# ESP_LoRa_1_1.net
KiCad netlist of a schematic drawn in EAGLE
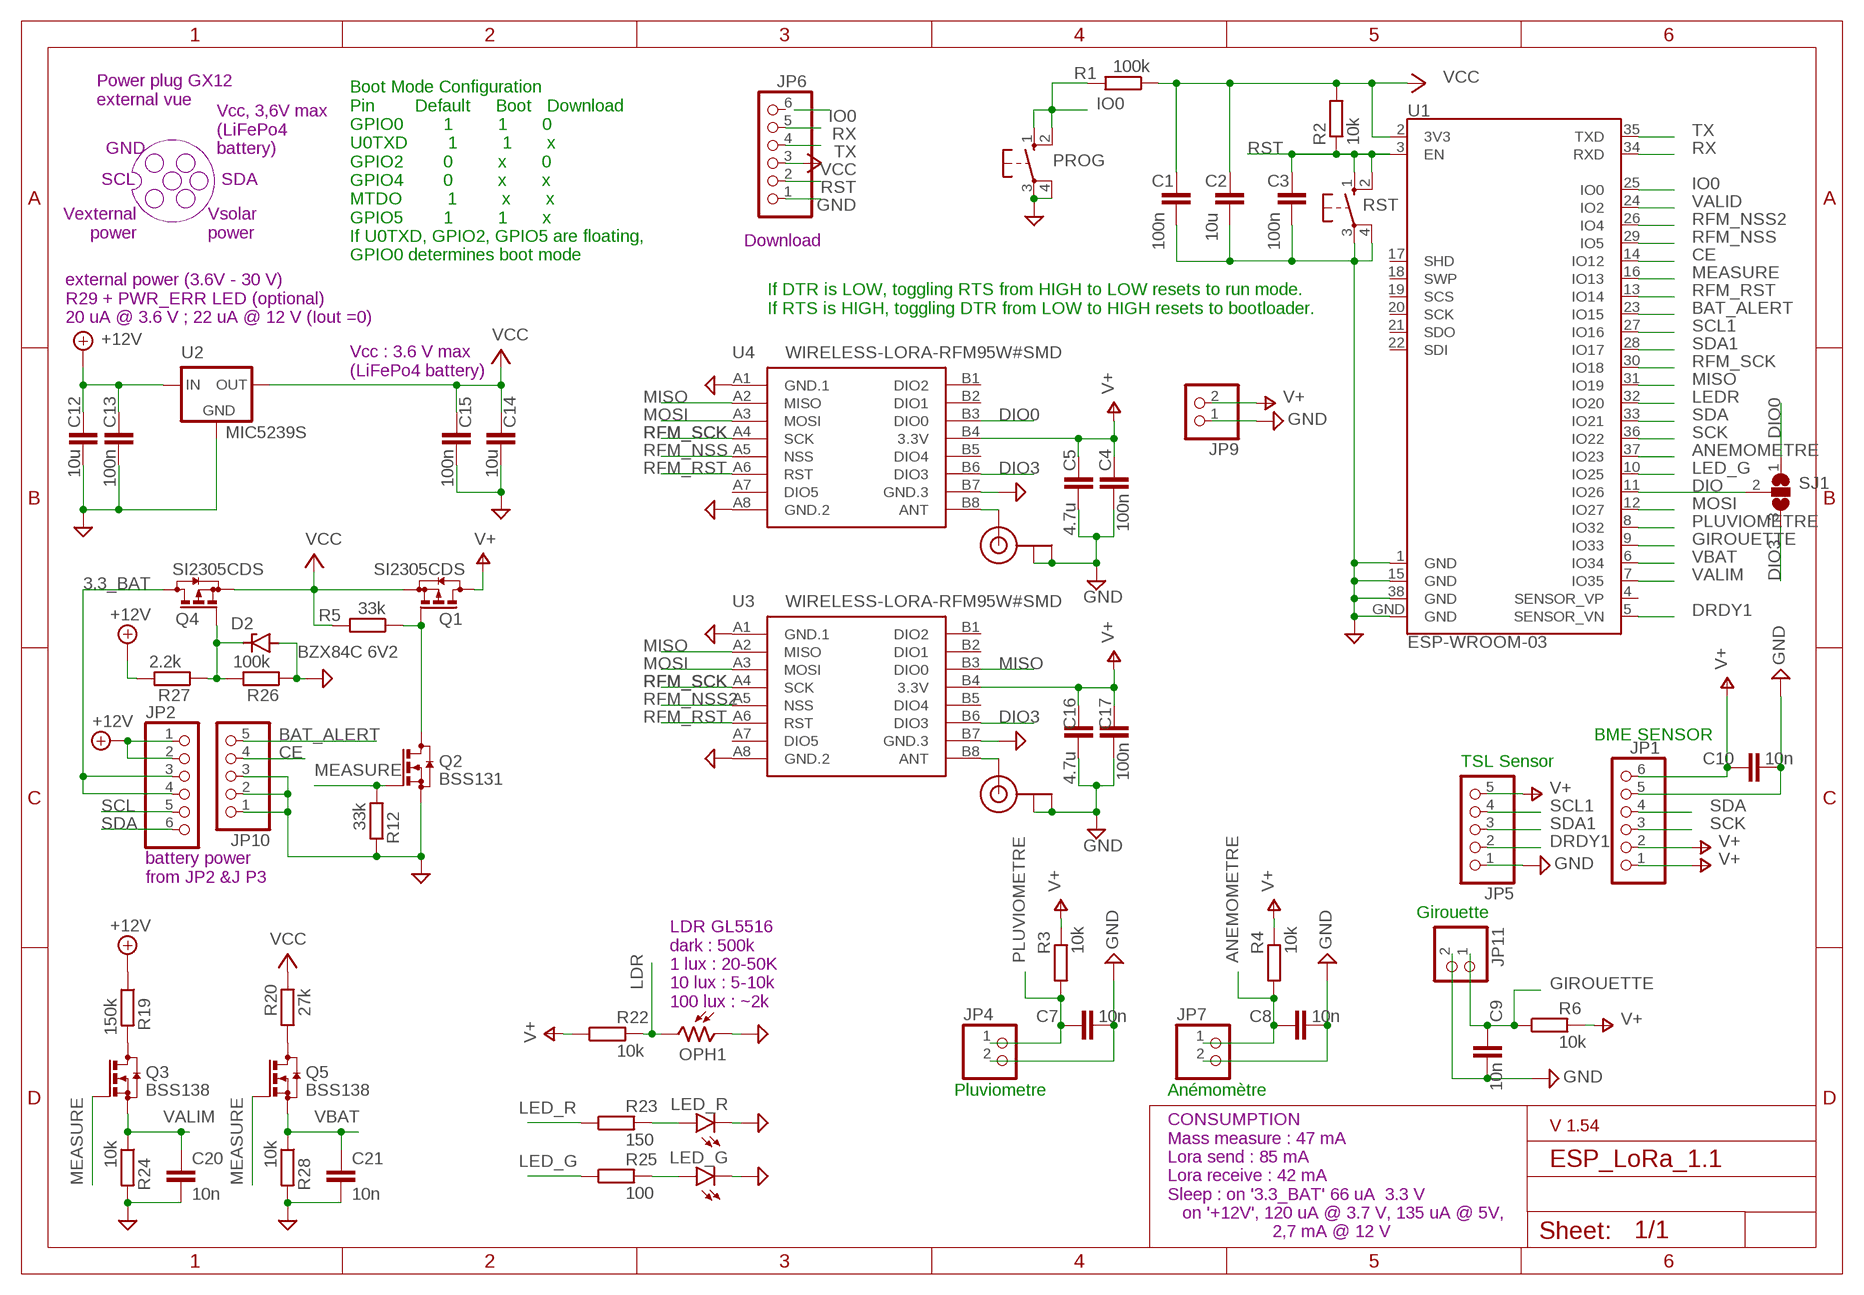
[diagram p0: schematic, sheet 1]

(export (version "E")
  (design (tool "Eeschema 10.0.6"))
  (components
    (comp (ref "C1")
      (value "100n")
      (footprint "eagle-import:C1206")
      (libsource (lib "eagle-import") (part "CC1206"))
    )
    (comp (ref "C2")
      (value "10u")
      (footprint "eagle-import:C1210")
      (libsource (lib "eagle-import") (part "CC1210"))
    )
    (comp (ref "C3")
      (value "100n")
      (footprint "eagle-import:C1206")
      (libsource (lib "eagle-import") (part "CC1206"))
    )
    (comp (ref "C4")
      (value "100n")
      (footprint "eagle-import:C1206")
      (libsource (lib "eagle-import") (part "CC1206"))
    )
    (comp (ref "C5")
      (value "4.7u")
      (footprint "eagle-import:C1210")
      (libsource (lib "eagle-import") (part "CC1210"))
    )
    (comp (ref "C7")
      (value "10n")
      (footprint "eagle-import:C1206")
      (libsource (lib "eagle-import") (part "CC1206"))
    )
    (comp (ref "C8")
      (value "10n")
      (footprint "eagle-import:C1206")
      (libsource (lib "eagle-import") (part "CC1206"))
    )
    (comp (ref "C9")
      (value "10n")
      (footprint "eagle-import:C1206")
      (libsource (lib "eagle-import") (part "CC1206"))
    )
    (comp (ref "C10")
      (value "10n")
      (footprint "eagle-import:C1206")
      (libsource (lib "eagle-import") (part "CC1206"))
    )
    (comp (ref "C12")
      (value "10u")
      (footprint "eagle-import:C1210")
      (libsource (lib "eagle-import") (part "CC1210"))
    )
    (comp (ref "C13")
      (value "100n")
      (footprint "eagle-import:C1206")
      (libsource (lib "eagle-import") (part "CC1206"))
    )
    (comp (ref "C14")
      (value "10u")
      (footprint "eagle-import:C1210")
      (libsource (lib "eagle-import") (part "CC1210"))
    )
    (comp (ref "C15")
      (value "100n")
      (footprint "eagle-import:C1206")
      (libsource (lib "eagle-import") (part "CC1206"))
    )
    (comp (ref "C16")
      (value "4.7u")
      (footprint "eagle-import:C1210")
      (libsource (lib "eagle-import") (part "CC1210"))
    )
    (comp (ref "C17")
      (value "100n")
      (footprint "eagle-import:C1206")
      (libsource (lib "eagle-import") (part "CC1206"))
    )
    (comp (ref "C20")
      (value "10n")
      (footprint "eagle-import:C1206")
      (libsource (lib "eagle-import") (part "CC1206"))
    )
    (comp (ref "C21")
      (value "10n")
      (footprint "eagle-import:C1206")
      (libsource (lib "eagle-import") (part "CC1206"))
    )
    (comp (ref "D2")
      (value "BZX84C 6V2")
      (footprint "eagle-import:TO236")
      (libsource (lib "eagle-import") (part "BZX84CSMD"))
    )
    (comp (ref "J1")
      (value "U.FL")
      (footprint "eagle-import:U.FL")
      (libsource (lib "eagle-import") (part "U.FL"))
    )
    (comp (ref "J2")
      (value "U.FL")
      (footprint "eagle-import:U.FL")
      (libsource (lib "eagle-import") (part "U.FL"))
    )
    (comp (ref "JP1")
      (value "PINHD-1X6")
      (footprint "eagle-import:1X06")
      (libsource (lib "eagle-import") (part "PINHD-1X6"))
    )
    (comp (ref "JP2")
      (value "PINHD-1X6")
      (footprint "eagle-import:1X06")
      (libsource (lib "eagle-import") (part "PINHD-1X6"))
    )
    (comp (ref "JP4")
      (value "PINHD-1X2")
      (footprint "eagle-import:1X02")
      (libsource (lib "eagle-import") (part "PINHD-1X2"))
    )
    (comp (ref "JP5")
      (value "PINHD-1X5")
      (footprint "eagle-import:1X05")
      (libsource (lib "eagle-import") (part "PINHD-1X5"))
    )
    (comp (ref "JP6")
      (value "PINHD-1X6")
      (footprint "eagle-import:1X06")
      (libsource (lib "eagle-import") (part "PINHD-1X6"))
    )
    (comp (ref "JP7")
      (value "PINHD-1X2")
      (footprint "eagle-import:1X02")
      (libsource (lib "eagle-import") (part "PINHD-1X2"))
    )
    (comp (ref "JP9")
      (value "PINHD-1X2")
      (footprint "eagle-import:1X02")
      (libsource (lib "eagle-import") (part "PINHD-1X2"))
    )
    (comp (ref "JP10")
      (value "PINHD-1X5")
      (footprint "eagle-import:1X05")
      (libsource (lib "eagle-import") (part "PINHD-1X5"))
    )
    (comp (ref "JP11")
      (value "PINHD-1X2")
      (footprint "eagle-import:1X02")
      (libsource (lib "eagle-import") (part "PINHD-1X2"))
    )
    (comp (ref "LED_G")
      (value "LEDSMT1206")
      (footprint "eagle-import:1206")
      (libsource (lib "eagle-import") (part "LEDSMT1206"))
    )
    (comp (ref "LED_R")
      (value "LEDSMT1206")
      (footprint "eagle-import:1206")
      (libsource (lib "eagle-import") (part "LEDSMT1206"))
    )
    (comp (ref "OPH1")
      (value "VT93N2")
      (footprint "eagle-import:VT900")
      (libsource (lib "eagle-import") (part "VT93N2"))
    )
    (comp (ref "PROG")
      (value "10-XX")
      (footprint "eagle-import:B3F-10XX")
      (fields (field (name "MPN") "B3F-1000"))
      (libsource (lib "eagle-import") (part "10-XX"))
    )
    (comp (ref "Q1")
      (value "SI2305CDS")
      (footprint "eagle-import:SOT23")
      (libsource (lib "eagle-import") (part "SI2305CDS"))
    )
    (comp (ref "Q2")
      (value "BSS131")
      (footprint "eagle-import:SOT23")
      (libsource (lib "eagle-import") (part "BSS131"))
    )
    (comp (ref "Q3")
      (value "BSS138")
      (footprint "eagle-import:SOT23")
      (libsource (lib "eagle-import") (part "BSS138"))
    )
    (comp (ref "Q4")
      (value "SI2305CDS")
      (footprint "eagle-import:SOT23")
      (libsource (lib "eagle-import") (part "SI2305CDS"))
    )
    (comp (ref "Q5")
      (value "BSS138")
      (footprint "eagle-import:SOT23")
      (libsource (lib "eagle-import") (part "BSS138"))
    )
    (comp (ref "R1")
      (value "100k")
      (footprint "eagle-import:R1206")
      (libsource (lib "eagle-import") (part "RR1206"))
    )
    (comp (ref "R2")
      (value "10k")
      (footprint "eagle-import:R1206")
      (libsource (lib "eagle-import") (part "RR1206"))
    )
    (comp (ref "R3")
      (value "10k")
      (footprint "eagle-import:R1206")
      (libsource (lib "eagle-import") (part "RR1206"))
    )
    (comp (ref "R4")
      (value "10k")
      (footprint "eagle-import:R1206")
      (libsource (lib "eagle-import") (part "RR1206"))
    )
    (comp (ref "R5")
      (value "33k")
      (footprint "eagle-import:R1206")
      (libsource (lib "eagle-import") (part "RR1206"))
    )
    (comp (ref "R6")
      (value "10k")
      (footprint "eagle-import:R1206")
      (libsource (lib "eagle-import") (part "RR1206"))
    )
    (comp (ref "R12")
      (value "33k")
      (footprint "eagle-import:R1206")
      (libsource (lib "eagle-import") (part "RR1206"))
    )
    (comp (ref "R19")
      (value "150k")
      (footprint "eagle-import:R1206")
      (libsource (lib "eagle-import") (part "RR1206"))
    )
    (comp (ref "R20")
      (value "27k")
      (footprint "eagle-import:R1206")
      (libsource (lib "eagle-import") (part "RR1206"))
    )
    (comp (ref "R22")
      (value "10k")
      (footprint "eagle-import:R1206")
      (libsource (lib "eagle-import") (part "RR1206"))
    )
    (comp (ref "R23")
      (value "150")
      (footprint "eagle-import:R1206")
      (libsource (lib "eagle-import") (part "RR1206"))
    )
    (comp (ref "R24")
      (value "10k")
      (footprint "eagle-import:R1206")
      (libsource (lib "eagle-import") (part "RR1206"))
    )
    (comp (ref "R25")
      (value "100")
      (footprint "eagle-import:R1206")
      (libsource (lib "eagle-import") (part "RR1206"))
    )
    (comp (ref "R26")
      (value "100k")
      (footprint "eagle-import:R1206")
      (libsource (lib "eagle-import") (part "RR1206"))
    )
    (comp (ref "R27")
      (value "2.2k")
      (footprint "eagle-import:R1206")
      (libsource (lib "eagle-import") (part "RR1206"))
    )
    (comp (ref "R28")
      (value "10k")
      (footprint "eagle-import:R1206")
      (libsource (lib "eagle-import") (part "RR1206"))
    )
    (comp (ref "RST")
      (value "10-XX")
      (footprint "eagle-import:B3F-10XX")
      (fields (field (name "MPN") "B3F-1000"))
      (libsource (lib "eagle-import") (part "10-XX"))
    )
    (comp (ref "SJ1")
      (value "SJ2W")
      (footprint "eagle-import:SJ_2")
      (libsource (lib "eagle-import") (part "SJ2W"))
    )
    (comp (ref "U1")
      (value "ESP-WROOM-03")
      (footprint "eagle-import:ESP-WROOM-03")
      (libsource (lib "eagle-import") (part "ESP-WROOM-03"))
    )
    (comp (ref "U2")
      (value "MIC5239S")
      (footprint "eagle-import:SOT223")
      (libsource (lib "eagle-import") (part "MIC5239S"))
    )
    (comp (ref "U3")
      (value "WIRELESS-LORA-RFM95W#SMD")
      (footprint "eagle-import:WIRELESS-LORA-RFM95W#SMD")
      (libsource (lib "eagle-import") (part "WIRELESS-LORA-RFM95W#SMD"))
    )
    (comp (ref "U4")
      (value "WIRELESS-LORA-RFM95W#SMD")
      (footprint "eagle-import:WIRELESS-LORA-RFM95W#SMD")
      (libsource (lib "eagle-import") (part "WIRELESS-LORA-RFM95W#SMD"))
    )
  )
  (nets
    (net (code "1") (name "+12V") (class "Default")
      (node (ref "C12") (pin "1") (pinfunction "1_1") (pintype "passive"))
      (node (ref "C13") (pin "1") (pinfunction "1_1") (pintype "passive"))
      (node (ref "JP2") (pin "1") (pinfunction "1_1") (pintype "passive"))
      (node (ref "JP2") (pin "2") (pinfunction "2_2") (pintype "passive"))
      (node (ref "R19") (pin "1") (pinfunction "1_1") (pintype "passive"))
      (node (ref "R27") (pin "2") (pinfunction "2_2") (pintype "passive"))
      (node (ref "U2") (pin "1") (pinfunction "IN_1") (pintype "input"))
    )
    (net (code "2") (name "/3.3_BAT") (class "Default")
      (node (ref "JP2") (pin "3") (pinfunction "3_3") (pintype "passive"))
      (node (ref "JP2") (pin "4") (pinfunction "4_4") (pintype "passive"))
      (node (ref "Q4") (pin "3") (pinfunction "D_3") (pintype "passive"))
    )
    (net (code "3") (name "/ANEMOMETRE") (class "Default")
      (node (ref "C8") (pin "1") (pinfunction "1_1") (pintype "passive"))
      (node (ref "JP7") (pin "1") (pinfunction "1_1") (pintype "passive"))
      (node (ref "R4") (pin "1") (pinfunction "1_1") (pintype "passive"))
      (node (ref "U1") (pin "37") (pinfunction "IO23_37") (pintype "bidirectional"))
    )
    (net (code "4") (name "/BAT_ALERT") (class "Default")
      (node (ref "JP10") (pin "5") (pinfunction "5_5") (pintype "passive"))
      (node (ref "U1") (pin "23") (pinfunction "IO15_23") (pintype "bidirectional"))
    )
    (net (code "5") (name "/CE") (class "Default")
      (node (ref "JP10") (pin "4") (pinfunction "4_4") (pintype "passive"))
      (node (ref "U1") (pin "14") (pinfunction "IO12_14") (pintype "bidirectional"))
    )
    (net (code "6") (name "/DIO") (class "Default")
      (node (ref "SJ1") (pin "2") (pinfunction "2_2") (pintype "passive"))
      (node (ref "U1") (pin "11") (pinfunction "IO26_11") (pintype "bidirectional"))
    )
    (net (code "7") (name "/DIO0") (class "Default")
      (node (ref "SJ1") (pin "1") (pinfunction "1_1") (pintype "passive"))
      (node (ref "U4") (pin "B3") (pinfunction "DIO0_B3") (pintype "bidirectional"))
    )
    (net (code "8") (name "/DIO3") (class "Default")
      (node (ref "SJ1") (pin "3") (pinfunction "3_3") (pintype "passive"))
      (node (ref "U3") (pin "B6") (pinfunction "DIO3_B6") (pintype "bidirectional"))
      (node (ref "U4") (pin "B6") (pinfunction "DIO3_B6") (pintype "bidirectional"))
    )
    (net (code "9") (name "/DRDY1") (class "Default")
      (node (ref "JP5") (pin "2") (pinfunction "2_2") (pintype "passive"))
      (node (ref "U1") (pin "5") (pinfunction "SENSOR_VN_5") (pintype "bidirectional"))
    )
    (net (code "10") (name "/GIROUETTE") (class "Default")
      (node (ref "C9") (pin "1") (pinfunction "1_1") (pintype "passive"))
      (node (ref "JP11") (pin "1") (pinfunction "1_1") (pintype "passive"))
      (node (ref "R6") (pin "1") (pinfunction "1_1") (pintype "passive"))
      (node (ref "U1") (pin "9") (pinfunction "IO33_9") (pintype "bidirectional"))
    )
    (net (code "11") (name "/IO0") (class "Default")
      (node (ref "PROG") (pin "1") (pinfunction "S_1") (pintype "passive"))
      (node (ref "PROG") (pin "2") (pinfunction "S1_2") (pintype "passive"))
      (node (ref "R1") (pin "2") (pinfunction "2_2") (pintype "passive"))
      (node (ref "U1") (pin "25") (pinfunction "IO0_25") (pintype "bidirectional"))
    )
    (net (code "12") (name "/LDR") (class "Default")
      (node (ref "OPH1") (pin "2") (pinfunction "2_2") (pintype "passive"))
      (node (ref "R22") (pin "2") (pinfunction "2_2") (pintype "passive"))
    )
    (net (code "13") (name "/LEDR") (class "Default")
      (node (ref "U1") (pin "32") (pinfunction "IO20_32") (pintype "bidirectional"))
    )
    (net (code "14") (name "/LED_G") (class "Default")
      (node (ref "R25") (pin "1") (pinfunction "1_1") (pintype "passive"))
      (node (ref "U1") (pin "10") (pinfunction "IO25_10") (pintype "bidirectional"))
    )
    (net (code "15") (name "/LED_R") (class "Default")
      (node (ref "R23") (pin "1") (pinfunction "1_1") (pintype "passive"))
    )
    (net (code "16") (name "/MEASURE") (class "Default")
      (node (ref "Q2") (pin "1") (pinfunction "G_1") (pintype "passive"))
      (node (ref "Q3") (pin "1") (pinfunction "G_1") (pintype "passive"))
      (node (ref "Q5") (pin "1") (pinfunction "G_1") (pintype "passive"))
      (node (ref "R12") (pin "1") (pinfunction "1_1") (pintype "passive"))
      (node (ref "U1") (pin "16") (pinfunction "IO13_16") (pintype "bidirectional"))
    )
    (net (code "17") (name "/MISO") (class "Default")
      (node (ref "U1") (pin "31") (pinfunction "IO19_31") (pintype "bidirectional"))
      (node (ref "U3") (pin "A2") (pinfunction "MISO_A2") (pintype "bidirectional"))
      (node (ref "U3") (pin "B3") (pinfunction "DIO0_B3") (pintype "bidirectional"))
      (node (ref "U4") (pin "A2") (pinfunction "MISO_A2") (pintype "bidirectional"))
    )
    (net (code "18") (name "/MOSI") (class "Default")
      (node (ref "U1") (pin "12") (pinfunction "IO27_12") (pintype "bidirectional"))
      (node (ref "U3") (pin "A3") (pinfunction "MOSI_A3") (pintype "bidirectional"))
      (node (ref "U4") (pin "A3") (pinfunction "MOSI_A3") (pintype "bidirectional"))
    )
    (net (code "19") (name "/PLUVIOMETRE") (class "Default")
      (node (ref "C7") (pin "1") (pinfunction "1_1") (pintype "passive"))
      (node (ref "JP4") (pin "1") (pinfunction "1_1") (pintype "passive"))
      (node (ref "R3") (pin "1") (pinfunction "1_1") (pintype "passive"))
      (node (ref "U1") (pin "8") (pinfunction "IO32_8") (pintype "bidirectional"))
    )
    (net (code "20") (name "/RFM_NSS") (class "Default")
      (node (ref "U1") (pin "29") (pinfunction "IO5_29") (pintype "bidirectional"))
      (node (ref "U4") (pin "A5") (pinfunction "NSS_A5") (pintype "bidirectional"))
    )
    (net (code "21") (name "/RFM_NSS2") (class "Default")
      (node (ref "U1") (pin "26") (pinfunction "IO4_26") (pintype "bidirectional"))
      (node (ref "U3") (pin "A5") (pinfunction "NSS_A5") (pintype "bidirectional"))
    )
    (net (code "22") (name "/RFM_RST") (class "Default")
      (node (ref "U1") (pin "13") (pinfunction "IO14_13") (pintype "bidirectional"))
      (node (ref "U3") (pin "A6") (pinfunction "RST_A6") (pintype "bidirectional"))
      (node (ref "U4") (pin "A6") (pinfunction "RST_A6") (pintype "bidirectional"))
    )
    (net (code "23") (name "/RFM_SCK") (class "Default")
      (node (ref "U1") (pin "30") (pinfunction "IO18_30") (pintype "bidirectional"))
      (node (ref "U3") (pin "A4") (pinfunction "SCK_A4") (pintype "bidirectional"))
      (node (ref "U4") (pin "A4") (pinfunction "SCK_A4") (pintype "bidirectional"))
    )
    (net (code "24") (name "/RST") (class "Default")
      (node (ref "C3") (pin "1") (pinfunction "1_1") (pintype "passive"))
      (node (ref "JP6") (pin "2") (pinfunction "2_2") (pintype "passive"))
      (node (ref "R2") (pin "1") (pinfunction "1_1") (pintype "passive"))
      (node (ref "RST") (pin "1") (pinfunction "S_1") (pintype "passive"))
      (node (ref "RST") (pin "2") (pinfunction "S1_2") (pintype "passive"))
      (node (ref "U1") (pin "3") (pinfunction "EN_3") (pintype "bidirectional"))
    )
    (net (code "25") (name "/RX") (class "Default")
      (node (ref "JP6") (pin "5") (pinfunction "5_5") (pintype "passive"))
      (node (ref "U1") (pin "34") (pinfunction "RXD_34") (pintype "bidirectional"))
    )
    (net (code "26") (name "/SCK") (class "Default")
      (node (ref "JP1") (pin "3") (pinfunction "3_3") (pintype "passive"))
      (node (ref "U1") (pin "36") (pinfunction "IO22_36") (pintype "bidirectional"))
    )
    (net (code "27") (name "/SCL") (class "Default")
      (node (ref "JP2") (pin "5") (pinfunction "5_5") (pintype "passive"))
    )
    (net (code "28") (name "/SCL1") (class "Default")
      (node (ref "JP5") (pin "4") (pinfunction "4_4") (pintype "passive"))
      (node (ref "U1") (pin "27") (pinfunction "IO16_27") (pintype "bidirectional"))
    )
    (net (code "29") (name "/SDA") (class "Default")
      (node (ref "JP1") (pin "4") (pinfunction "4_4") (pintype "passive"))
      (node (ref "JP2") (pin "6") (pinfunction "6_6") (pintype "passive"))
      (node (ref "U1") (pin "33") (pinfunction "IO21_33") (pintype "bidirectional"))
    )
    (net (code "30") (name "/SDA1") (class "Default")
      (node (ref "JP5") (pin "3") (pinfunction "3_3") (pintype "passive"))
      (node (ref "U1") (pin "28") (pinfunction "IO17_28") (pintype "bidirectional"))
    )
    (net (code "31") (name "/TX") (class "Default")
      (node (ref "JP6") (pin "4") (pinfunction "4_4") (pintype "passive"))
      (node (ref "U1") (pin "35") (pinfunction "TXD_35") (pintype "bidirectional"))
    )
    (net (code "32") (name "/VALID") (class "Default")
      (node (ref "U1") (pin "24") (pinfunction "IO2_24") (pintype "bidirectional"))
    )
    (net (code "33") (name "/VALIM") (class "Default")
      (node (ref "C20") (pin "1") (pinfunction "1_1") (pintype "passive"))
      (node (ref "Q3") (pin "2") (pinfunction "S_2") (pintype "passive"))
      (node (ref "R24") (pin "1") (pinfunction "1_1") (pintype "passive"))
      (node (ref "U1") (pin "7") (pinfunction "IO35_7") (pintype "bidirectional"))
    )
    (net (code "34") (name "/VBAT") (class "Default")
      (node (ref "C21") (pin "1") (pinfunction "1_1") (pintype "passive"))
      (node (ref "Q5") (pin "2") (pinfunction "S_2") (pintype "passive"))
      (node (ref "R28") (pin "1") (pinfunction "1_1") (pintype "passive"))
      (node (ref "U1") (pin "6") (pinfunction "IO34_6") (pintype "bidirectional"))
    )
    (net (code "35") (name "GND") (class "Default")
      (node (ref "C1") (pin "2") (pinfunction "2_2") (pintype "passive"))
      (node (ref "C10") (pin "2") (pinfunction "2_2") (pintype "passive"))
      (node (ref "C12") (pin "2") (pinfunction "2_2") (pintype "passive"))
      (node (ref "C13") (pin "2") (pinfunction "2_2") (pintype "passive"))
      (node (ref "C14") (pin "2") (pinfunction "2_2") (pintype "passive"))
      (node (ref "C15") (pin "2") (pinfunction "2_2") (pintype "passive"))
      (node (ref "C16") (pin "2") (pinfunction "2_2") (pintype "passive"))
      (node (ref "C17") (pin "2") (pinfunction "2_2") (pintype "passive"))
      (node (ref "C2") (pin "2") (pinfunction "2_2") (pintype "passive"))
      (node (ref "C20") (pin "2") (pinfunction "2_2") (pintype "passive"))
      (node (ref "C21") (pin "2") (pinfunction "2_2") (pintype "passive"))
      (node (ref "C3") (pin "2") (pinfunction "2_2") (pintype "passive"))
      (node (ref "C4") (pin "2") (pinfunction "2_2") (pintype "passive"))
      (node (ref "C5") (pin "2") (pinfunction "2_2") (pintype "passive"))
      (node (ref "C7") (pin "2") (pinfunction "2_2") (pintype "passive"))
      (node (ref "C8") (pin "2") (pinfunction "2_2") (pintype "passive"))
      (node (ref "C9") (pin "2") (pinfunction "2_2") (pintype "passive"))
      (node (ref "D2") (pin "A") (pinfunction "A_A") (pintype "passive"))
      (node (ref "J1") (pin "1") (pinfunction "GND_1") (pintype "passive"))
      (node (ref "J1") (pin "2") (pinfunction "GND_2") (pintype "passive"))
      (node (ref "J2") (pin "1") (pinfunction "GND_1") (pintype "passive"))
      (node (ref "J2") (pin "2") (pinfunction "GND_2") (pintype "passive"))
      (node (ref "JP1") (pin "5") (pinfunction "5_5") (pintype "passive"))
      (node (ref "JP10") (pin "1") (pinfunction "1_1") (pintype "passive"))
      (node (ref "JP10") (pin "2") (pinfunction "2_2") (pintype "passive"))
      (node (ref "JP10") (pin "3") (pinfunction "3_3") (pintype "passive"))
      (node (ref "JP11") (pin "2") (pinfunction "2_2") (pintype "passive"))
      (node (ref "JP4") (pin "2") (pinfunction "2_2") (pintype "passive"))
      (node (ref "JP5") (pin "1") (pinfunction "1_1") (pintype "passive"))
      (node (ref "JP6") (pin "1") (pinfunction "1_1") (pintype "passive"))
      (node (ref "JP7") (pin "2") (pinfunction "2_2") (pintype "passive"))
      (node (ref "JP9") (pin "1") (pinfunction "1_1") (pintype "passive"))
      (node (ref "LED_G") (pin "C") (pinfunction "C_C") (pintype "passive"))
      (node (ref "LED_R") (pin "C") (pinfunction "C_C") (pintype "passive"))
      (node (ref "OPH1") (pin "1") (pinfunction "1_1") (pintype "passive"))
      (node (ref "PROG") (pin "3") (pinfunction "P_3") (pintype "passive"))
      (node (ref "PROG") (pin "4") (pinfunction "P1_4") (pintype "passive"))
      (node (ref "Q2") (pin "2") (pinfunction "S_2") (pintype "passive"))
      (node (ref "R12") (pin "2") (pinfunction "2_2") (pintype "passive"))
      (node (ref "R24") (pin "2") (pinfunction "2_2") (pintype "passive"))
      (node (ref "R26") (pin "1") (pinfunction "1_1") (pintype "passive"))
      (node (ref "R28") (pin "2") (pinfunction "2_2") (pintype "passive"))
      (node (ref "RST") (pin "3") (pinfunction "P_3") (pintype "passive"))
      (node (ref "RST") (pin "4") (pinfunction "P1_4") (pintype "passive"))
      (node (ref "U1") (pin "1") (pinfunction "GND_1") (pintype "bidirectional"))
      (node (ref "U1") (pin "15") (pinfunction "GND_15") (pintype "bidirectional"))
      (node (ref "U1") (pin "38") (pinfunction "GND_38") (pintype "bidirectional"))
      (node (ref "U1") (pin "GND") (pinfunction "GND_GND") (pintype "bidirectional"))
      (node (ref "U2") (pin "2") (pinfunction "GND_2") (pintype "passive"))
      (node (ref "U2") (pin "4") (pinfunction "GND_4") (pintype "passive"))
      (node (ref "U3") (pin "A1") (pinfunction "GND.1_A1") (pintype "power_in"))
      (node (ref "U3") (pin "A8") (pinfunction "GND.2_A8") (pintype "power_in"))
      (node (ref "U3") (pin "B7") (pinfunction "GND.3_B7") (pintype "power_in"))
      (node (ref "U4") (pin "A1") (pinfunction "GND.1_A1") (pintype "power_in"))
      (node (ref "U4") (pin "A8") (pinfunction "GND.2_A8") (pintype "power_in"))
      (node (ref "U4") (pin "B7") (pinfunction "GND.3_B7") (pintype "power_in"))
    )
    (net (code "36") (name "Net-(J1-SIGNAL)") (class "Default")
      (node (ref "J1") (pin "3") (pinfunction "SIGNAL_3") (pintype "passive"))
      (node (ref "U3") (pin "B8") (pinfunction "ANT_B8") (pintype "passive"))
    )
    (net (code "37") (name "Net-(J2-SIGNAL)") (class "Default")
      (node (ref "J2") (pin "3") (pinfunction "SIGNAL_3") (pintype "passive"))
      (node (ref "U4") (pin "B8") (pinfunction "ANT_B8") (pintype "passive"))
    )
    (net (code "38") (name "Net-(LED_G-PadA)") (class "Default")
      (node (ref "LED_G") (pin "A") (pinfunction "A_A") (pintype "passive"))
      (node (ref "R25") (pin "2") (pinfunction "2_2") (pintype "passive"))
    )
    (net (code "39") (name "Net-(LED_R-PadA)") (class "Default")
      (node (ref "LED_R") (pin "A") (pinfunction "A_A") (pintype "passive"))
      (node (ref "R23") (pin "2") (pinfunction "2_2") (pintype "passive"))
    )
    (net (code "40") (name "Net-(Q1-G)") (class "Default")
      (node (ref "Q1") (pin "1") (pinfunction "G_1") (pintype "passive"))
      (node (ref "Q2") (pin "3") (pinfunction "D_3") (pintype "passive"))
      (node (ref "R5") (pin "1") (pinfunction "1_1") (pintype "passive"))
    )
    (net (code "41") (name "Net-(Q3-D)") (class "Default")
      (node (ref "Q3") (pin "3") (pinfunction "D_3") (pintype "passive"))
      (node (ref "R19") (pin "2") (pinfunction "2_2") (pintype "passive"))
    )
    (net (code "42") (name "Net-(Q4-G)") (class "Default")
      (node (ref "D2") (pin "C") (pinfunction "C_C") (pintype "passive"))
      (node (ref "Q4") (pin "1") (pinfunction "G_1") (pintype "passive"))
      (node (ref "R26") (pin "2") (pinfunction "2_2") (pintype "passive"))
      (node (ref "R27") (pin "1") (pinfunction "1_1") (pintype "passive"))
    )
    (net (code "43") (name "Net-(Q5-D)") (class "Default")
      (node (ref "Q5") (pin "3") (pinfunction "D_3") (pintype "passive"))
      (node (ref "R20") (pin "1") (pinfunction "1_1") (pintype "passive"))
    )
    (net (code "44") (name "V+") (class "Default")
      (node (ref "C10") (pin "1") (pinfunction "1_1") (pintype "passive"))
      (node (ref "C16") (pin "1") (pinfunction "1_1") (pintype "passive"))
      (node (ref "C17") (pin "1") (pinfunction "1_1") (pintype "passive"))
      (node (ref "C4") (pin "1") (pinfunction "1_1") (pintype "passive"))
      (node (ref "C5") (pin "1") (pinfunction "1_1") (pintype "passive"))
      (node (ref "JP1") (pin "1") (pinfunction "1_1") (pintype "passive"))
      (node (ref "JP1") (pin "2") (pinfunction "2_2") (pintype "passive"))
      (node (ref "JP1") (pin "6") (pinfunction "6_6") (pintype "passive"))
      (node (ref "JP5") (pin "5") (pinfunction "5_5") (pintype "passive"))
      (node (ref "JP9") (pin "2") (pinfunction "2_2") (pintype "passive"))
      (node (ref "Q1") (pin "3") (pinfunction "D_3") (pintype "passive"))
      (node (ref "R22") (pin "1") (pinfunction "1_1") (pintype "passive"))
      (node (ref "R3") (pin "2") (pinfunction "2_2") (pintype "passive"))
      (node (ref "R4") (pin "2") (pinfunction "2_2") (pintype "passive"))
      (node (ref "R6") (pin "2") (pinfunction "2_2") (pintype "passive"))
      (node (ref "U3") (pin "B4") (pinfunction "3.3V_B4") (pintype "power_in"))
      (node (ref "U4") (pin "B4") (pinfunction "3.3V_B4") (pintype "power_in"))
    )
    (net (code "45") (name "VCC") (class "Default")
      (node (ref "C1") (pin "1") (pinfunction "1_1") (pintype "passive"))
      (node (ref "C14") (pin "1") (pinfunction "1_1") (pintype "passive"))
      (node (ref "C15") (pin "1") (pinfunction "1_1") (pintype "passive"))
      (node (ref "C2") (pin "1") (pinfunction "1_1") (pintype "passive"))
      (node (ref "JP6") (pin "3") (pinfunction "3_3") (pintype "passive"))
      (node (ref "Q1") (pin "2") (pinfunction "S_2") (pintype "passive"))
      (node (ref "Q4") (pin "2") (pinfunction "S_2") (pintype "passive"))
      (node (ref "R1") (pin "1") (pinfunction "1_1") (pintype "passive"))
      (node (ref "R2") (pin "2") (pinfunction "2_2") (pintype "passive"))
      (node (ref "R20") (pin "2") (pinfunction "2_2") (pintype "passive"))
      (node (ref "R5") (pin "2") (pinfunction "2_2") (pintype "passive"))
      (node (ref "U1") (pin "2") (pinfunction "3V3_2") (pintype "bidirectional"))
      (node (ref "U2") (pin "3") (pinfunction "OUT_3") (pintype "passive"))
    )
    (net (code "46") (name "unconnected-(JP6-Pad6)") (class "Default")
      (node (ref "JP6") (pin "6") (pinfunction "6_6") (pintype "passive"))
    )
    (net (code "47") (name "unconnected-(U1-SCK-Pad20)") (class "Default")
      (node (ref "U1") (pin "20") (pinfunction "SCK_20") (pintype "bidirectional"))
    )
    (net (code "48") (name "unconnected-(U1-SCS-Pad19)") (class "Default")
      (node (ref "U1") (pin "19") (pinfunction "SCS_19") (pintype "bidirectional"))
    )
    (net (code "49") (name "unconnected-(U1-SDI-Pad22)") (class "Default")
      (node (ref "U1") (pin "22") (pinfunction "SDI_22") (pintype "bidirectional"))
    )
    (net (code "50") (name "unconnected-(U1-SDO-Pad21)") (class "Default")
      (node (ref "U1") (pin "21") (pinfunction "SDO_21") (pintype "bidirectional"))
    )
    (net (code "51") (name "unconnected-(U1-SENSOR_VP-Pad4)") (class "Default")
      (node (ref "U1") (pin "4") (pinfunction "SENSOR_VP_4") (pintype "bidirectional"))
    )
    (net (code "52") (name "unconnected-(U1-SHD-Pad17)") (class "Default")
      (node (ref "U1") (pin "17") (pinfunction "SHD_17") (pintype "bidirectional"))
    )
    (net (code "53") (name "unconnected-(U1-SWP-Pad18)") (class "Default")
      (node (ref "U1") (pin "18") (pinfunction "SWP_18") (pintype "bidirectional"))
    )
    (net (code "54") (name "unconnected-(U3-DIO1-PadB2)") (class "Default")
      (node (ref "U3") (pin "B2") (pinfunction "DIO1_B2") (pintype "bidirectional"))
    )
    (net (code "55") (name "unconnected-(U3-DIO2-PadB1)") (class "Default")
      (node (ref "U3") (pin "B1") (pinfunction "DIO2_B1") (pintype "bidirectional"))
    )
    (net (code "56") (name "unconnected-(U3-DIO4-PadB5)") (class "Default")
      (node (ref "U3") (pin "B5") (pinfunction "DIO4_B5") (pintype "bidirectional"))
    )
    (net (code "57") (name "unconnected-(U3-DIO5-PadA7)") (class "Default")
      (node (ref "U3") (pin "A7") (pinfunction "DIO5_A7") (pintype "bidirectional"))
    )
    (net (code "58") (name "unconnected-(U4-DIO1-PadB2)") (class "Default")
      (node (ref "U4") (pin "B2") (pinfunction "DIO1_B2") (pintype "bidirectional"))
    )
    (net (code "59") (name "unconnected-(U4-DIO2-PadB1)") (class "Default")
      (node (ref "U4") (pin "B1") (pinfunction "DIO2_B1") (pintype "bidirectional"))
    )
    (net (code "60") (name "unconnected-(U4-DIO4-PadB5)") (class "Default")
      (node (ref "U4") (pin "B5") (pinfunction "DIO4_B5") (pintype "bidirectional"))
    )
    (net (code "61") (name "unconnected-(U4-DIO5-PadA7)") (class "Default")
      (node (ref "U4") (pin "A7") (pinfunction "DIO5_A7") (pintype "bidirectional"))
    )
  )
)
